# Gravador_18F.net
KiCad netlist of a schematic drawn in EAGLE
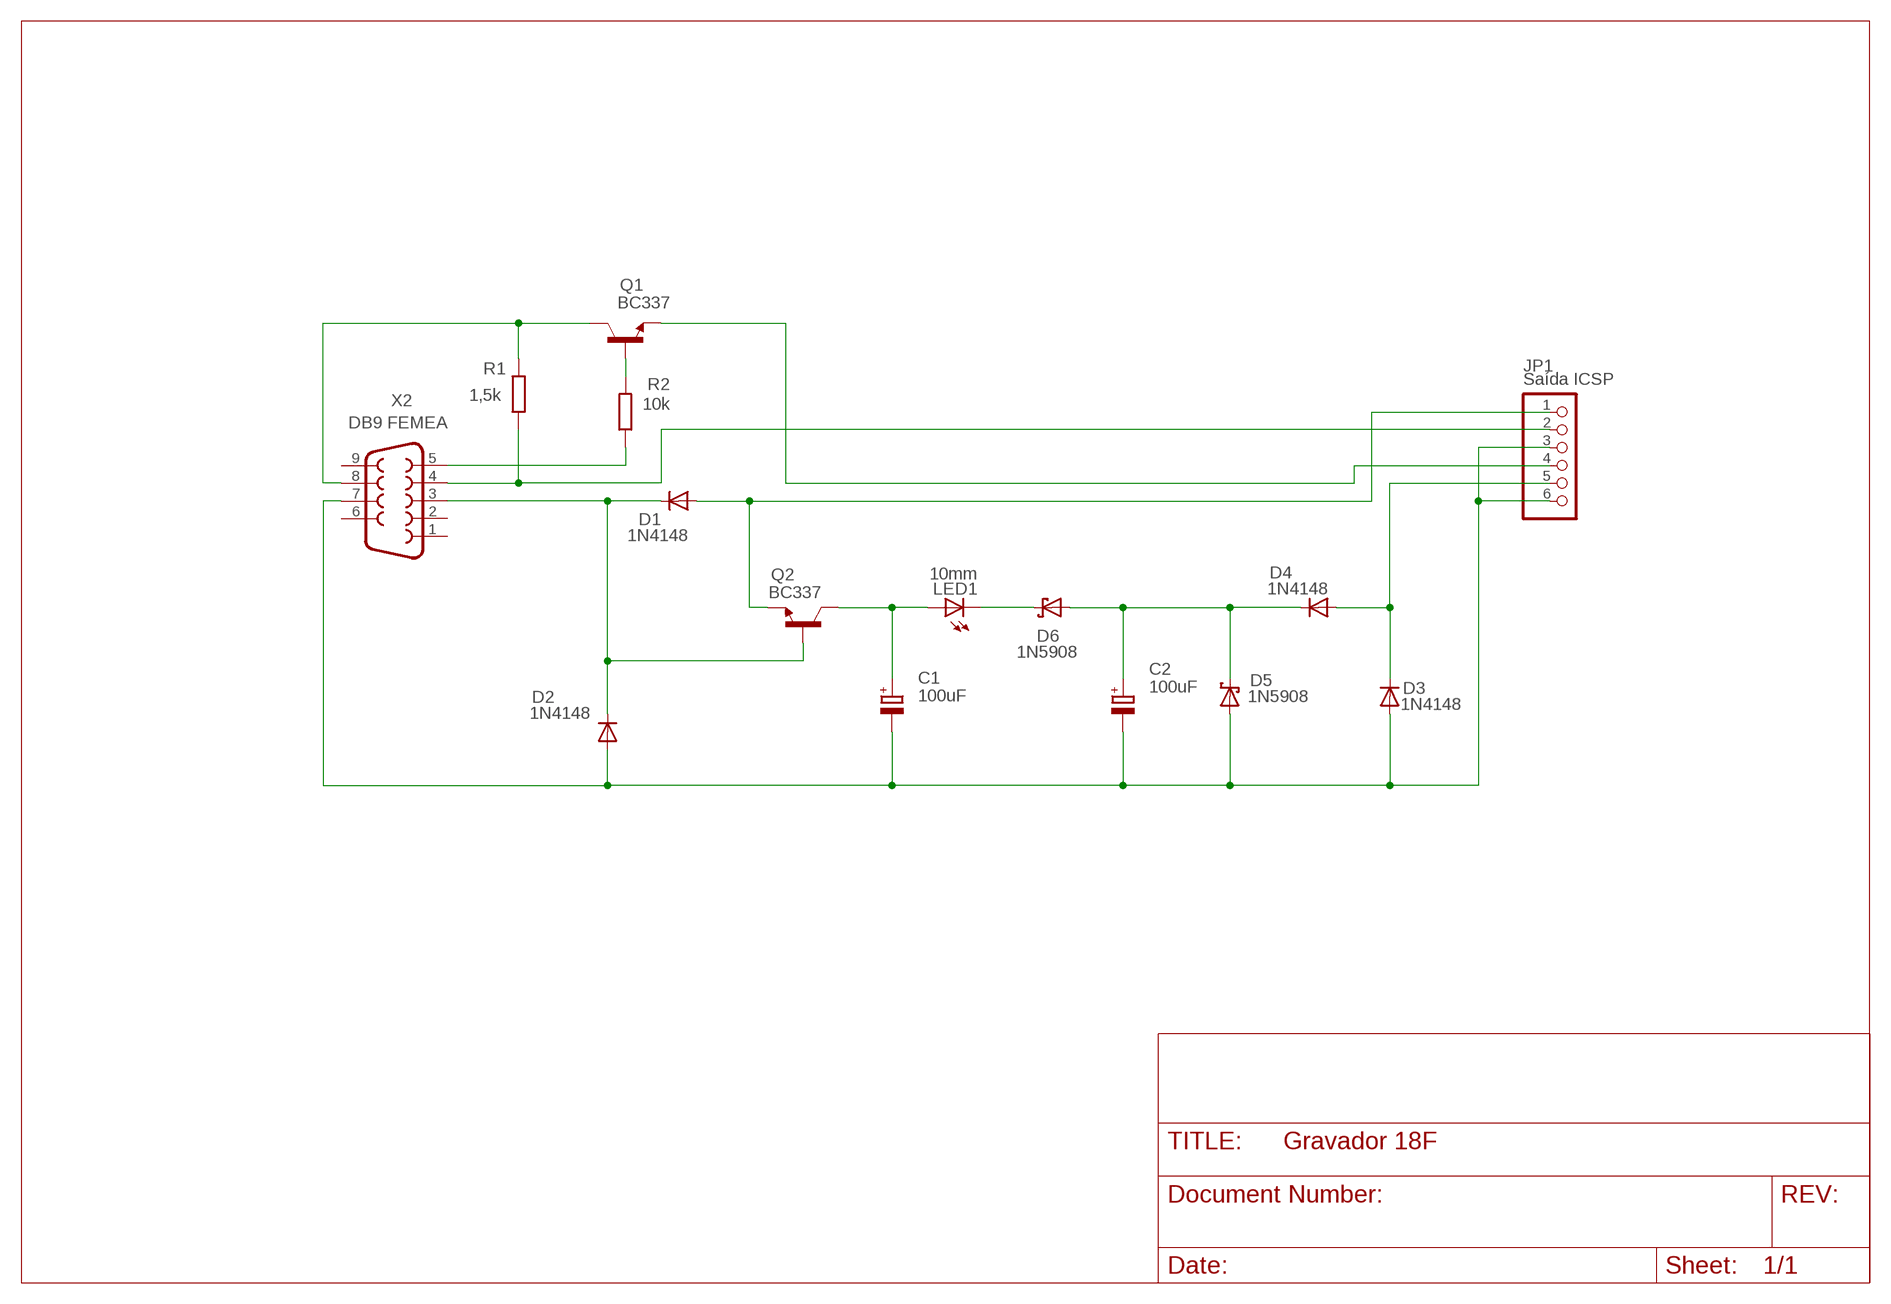
[diagram p0: schematic, sheet 1]

(export (version "E")
  (design (tool "Eeschema 10.0.6"))
  (components
    (comp (ref "C1")
      (value "100uF")
      (footprint "eagle-import:E3,5-10")
      (libsource (lib "eagle-import") (part "CPOL-EUE3.5-10"))
    )
    (comp (ref "C2")
      (value "100uF")
      (footprint "eagle-import:E3,5-10")
      (libsource (lib "eagle-import") (part "CPOL-EUE3.5-10"))
    )
    (comp (ref "D1")
      (value "1N4148")
      (footprint "eagle-import:DO35-7")
      (libsource (lib "eagle-import") (part "1N4148DO35-7"))
    )
    (comp (ref "D2")
      (value "1N4148")
      (footprint "eagle-import:DO35-7")
      (libsource (lib "eagle-import") (part "1N4148DO35-7"))
    )
    (comp (ref "D3")
      (value "1N4148")
      (footprint "eagle-import:DO35-7")
      (libsource (lib "eagle-import") (part "1N4148DO35-7"))
    )
    (comp (ref "D4")
      (value "1N4148")
      (footprint "eagle-import:DO35-7")
      (libsource (lib "eagle-import") (part "1N4148DO35-7"))
    )
    (comp (ref "D5")
      (value "1N5908")
      (footprint "eagle-import:C4111-15")
      (libsource (lib "eagle-import") (part "1N5908"))
    )
    (comp (ref "D6")
      (value "1N5908")
      (footprint "eagle-import:C4111-15")
      (libsource (lib "eagle-import") (part "1N5908"))
    )
    (comp (ref "JP1")
      (value "Saída ICSP")
      (footprint "eagle-import:1X06")
      (libsource (lib "eagle-import") (part "PINHD-1X6"))
    )
    (comp (ref "LED1")
      (value "10mm")
      (footprint "eagle-import:LED10MM")
      (libsource (lib "eagle-import") (part "LED10MM"))
    )
    (comp (ref "Q1")
      (value "BC337")
      (footprint "eagle-import:TO92")
      (libsource (lib "eagle-import") (part "BC337"))
    )
    (comp (ref "Q2")
      (value "BC337")
      (footprint "eagle-import:TO92")
      (libsource (lib "eagle-import") (part "BC337"))
    )
    (comp (ref "R1")
      (value "1,5k")
      (footprint "eagle-import:0207_7")
      (libsource (lib "eagle-import") (part "R-EU_0207/7"))
    )
    (comp (ref "R2")
      (value "10k")
      (footprint "eagle-import:0207_7")
      (libsource (lib "eagle-import") (part "R-EU_0207/7"))
    )
    (comp (ref "X2")
      (value "DB9 FEMEA")
      (footprint "eagle-import:F09HP")
      (libsource (lib "eagle-import") (part "F09HP"))
    )
  )
  (nets
    (net (code "1") (name "Net-(C1-Pad-)") (class "Default")
      (node (ref "C1") (pin "-") (pinfunction "-_-") (pintype "passive"))
      (node (ref "C2") (pin "-") (pinfunction "-_-") (pintype "passive"))
      (node (ref "D2") (pin "A") (pinfunction "A_A") (pintype "passive"))
      (node (ref "D3") (pin "A") (pinfunction "A_A") (pintype "passive"))
      (node (ref "D5") (pin "A") (pinfunction "A_A") (pintype "passive"))
      (node (ref "JP1") (pin "3") (pinfunction "3_3") (pintype "passive"))
      (node (ref "JP1") (pin "6") (pinfunction "6_6") (pintype "passive"))
      (node (ref "X2") (pin "7") (pinfunction "7_7") (pintype "passive"))
    )
    (net (code "2") (name "Net-(C2-Pad+)") (class "Default")
      (node (ref "C2") (pin "+") (pinfunction "+_+") (pintype "passive"))
      (node (ref "D4") (pin "C") (pinfunction "C_C") (pintype "passive"))
      (node (ref "D5") (pin "C") (pinfunction "C_C") (pintype "passive"))
      (node (ref "D6") (pin "A") (pinfunction "A_A") (pintype "passive"))
    )
    (net (code "3") (name "Net-(D3-PadC)") (class "Default")
      (node (ref "D3") (pin "C") (pinfunction "C_C") (pintype "passive"))
      (node (ref "D4") (pin "A") (pinfunction "A_A") (pintype "passive"))
      (node (ref "JP1") (pin "5") (pinfunction "5_5") (pintype "passive"))
    )
    (net (code "4") (name "Net-(JP1-Pad2)") (class "Default")
      (node (ref "JP1") (pin "2") (pinfunction "2_2") (pintype "passive"))
      (node (ref "R1") (pin "1") (pinfunction "1_1") (pintype "passive"))
      (node (ref "X2") (pin "4") (pinfunction "4_4") (pintype "passive"))
    )
    (net (code "5") (name "Net-(LED1-C)") (class "Default")
      (node (ref "D6") (pin "C") (pinfunction "C_C") (pintype "passive"))
      (node (ref "LED1") (pin "K") (pinfunction "C_K") (pintype "passive"))
    )
    (net (code "6") (name "Net-(Q1-B)") (class "Default")
      (node (ref "Q1") (pin "2") (pinfunction "B_2") (pintype "passive"))
      (node (ref "R2") (pin "2") (pinfunction "2_2") (pintype "passive"))
    )
    (net (code "7") (name "Net-(Q1-C)") (class "Default")
      (node (ref "Q1") (pin "3") (pinfunction "C_3") (pintype "passive"))
      (node (ref "R1") (pin "2") (pinfunction "2_2") (pintype "passive"))
      (node (ref "X2") (pin "8") (pinfunction "8_8") (pintype "passive"))
    )
    (net (code "8") (name "Net-(Q1-E)") (class "Default")
      (node (ref "JP1") (pin "4") (pinfunction "4_4") (pintype "passive"))
      (node (ref "Q1") (pin "1") (pinfunction "E_1") (pintype "passive"))
    )
    (net (code "9") (name "Net-(Q2-B)") (class "Default")
      (node (ref "D1") (pin "C") (pinfunction "C_C") (pintype "passive"))
      (node (ref "D2") (pin "C") (pinfunction "C_C") (pintype "passive"))
      (node (ref "Q2") (pin "2") (pinfunction "B_2") (pintype "passive"))
      (node (ref "X2") (pin "3") (pinfunction "3_3") (pintype "passive"))
    )
    (net (code "10") (name "Net-(Q2-C)") (class "Default")
      (node (ref "C1") (pin "+") (pinfunction "+_+") (pintype "passive"))
      (node (ref "LED1") (pin "A") (pinfunction "A_A") (pintype "passive"))
      (node (ref "Q2") (pin "3") (pinfunction "C_3") (pintype "passive"))
    )
    (net (code "11") (name "Net-(Q2-E)") (class "Default")
      (node (ref "D1") (pin "A") (pinfunction "A_A") (pintype "passive"))
      (node (ref "JP1") (pin "1") (pinfunction "1_1") (pintype "passive"))
      (node (ref "Q2") (pin "1") (pinfunction "E_1") (pintype "passive"))
    )
    (net (code "12") (name "Net-(R2-Pad1)") (class "Default")
      (node (ref "R2") (pin "1") (pinfunction "1_1") (pintype "passive"))
      (node (ref "X2") (pin "5") (pinfunction "5_5") (pintype "passive"))
    )
    (net (code "13") (name "unconnected-(X2-Pad1)") (class "Default")
      (node (ref "X2") (pin "1") (pinfunction "1_1") (pintype "passive"))
    )
    (net (code "14") (name "unconnected-(X2-Pad2)") (class "Default")
      (node (ref "X2") (pin "2") (pinfunction "2_2") (pintype "passive"))
    )
    (net (code "15") (name "unconnected-(X2-Pad6)") (class "Default")
      (node (ref "X2") (pin "6") (pinfunction "6_6") (pintype "passive"))
    )
    (net (code "16") (name "unconnected-(X2-Pad9)") (class "Default")
      (node (ref "X2") (pin "9") (pinfunction "9_9") (pintype "passive"))
    )
  )
)
